# PAC1720_Breakout.net
KiCad netlist of a schematic drawn in EAGLE
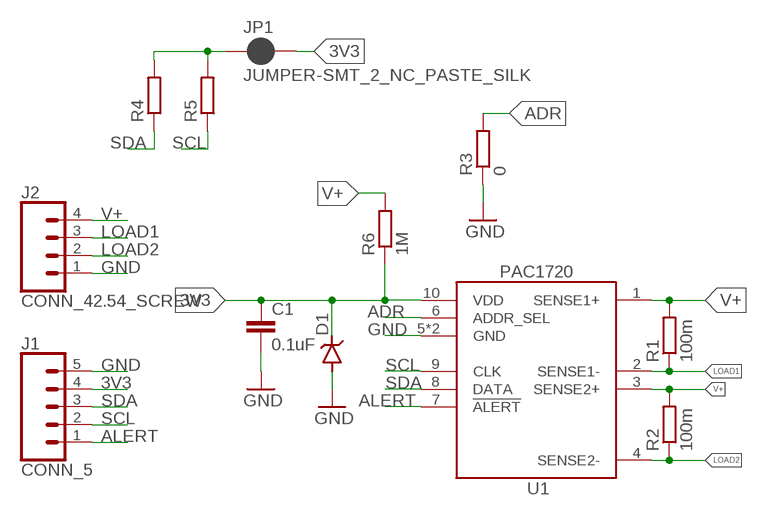
[diagram p0: schematic, sheet 1]

(export (version "E")
  (design (tool "Eeschema 10.0.6"))
  (components
    (comp (ref "C1")
      (value "0.1uF")
      (footprint "eagle-import:C0402")
      (fields (field (name "MF") "Murata") (field (name "MPN") "GCM155R71C104KA55D"))
      (libsource (lib "eagle-import") (part "C-EUC04020.1UF"))
    )
    (comp (ref "D1")
      (value "DIODE_ZENERSOD-123")
      (footprint "eagle-import:SOD-123")
      (fields
        (field (name "DIGIKEY") "MMSZ5231B-FDICT-ND")
        (field (name "MF") "Diodes Incorporated")
        (field (name "MPN") "MMSZ5231B-7-F")
      )
      (libsource (lib "eagle-import") (part "DIODE_ZENERSOD-123"))
    )
    (comp (ref "J1")
      (value "CONN_5")
      (footprint "eagle-import:1X05")
      (fields (field (name "MF") "On Shore") (field (name "MPN") "OSTVN05A150"))
      (libsource (lib "eagle-import") (part "CONN_5"))
    )
    (comp (ref "J2")
      (value "CONN_42.54_SCREW")
      (footprint "eagle-import:1X04_SCREW")
      (fields (field (name "MF") "On Shore") (field (name "MPN") "OSTVN04A150"))
      (libsource (lib "eagle-import") (part "CONN_42.54_SCREW"))
    )
    (comp (ref "JP1")
      (value "JUMPER-SMT_2_NC_PASTE_SILK")
      (footprint "eagle-import:SMT-JUMPER_2_NC_PASTE_SILK")
      (libsource (lib "eagle-import") (part "JUMPER-SMT_2_NC_PASTE_SILK"))
    )
    (comp (ref "R1")
      (value "100m")
      (footprint "eagle-import:R0805")
      (fields (field (name "MF") "Panasonic") (field (name "MPN") "ERJ-6DSFR10V"))
      (libsource (lib "eagle-import") (part "R-EU_R08050.1"))
    )
    (comp (ref "R2")
      (value "100m")
      (footprint "eagle-import:R0805")
      (fields (field (name "MF") "Panasonic") (field (name "MPN") "ERJ-6DSFR10V"))
      (libsource (lib "eagle-import") (part "R-EU_R08050.1"))
    )
    (comp (ref "R3")
      (value "0")
      (footprint "eagle-import:R0402")
      (fields (field (name "MF") "Yageo") (field (name "MPN") "RC0402JR-070RL"))
      (libsource (lib "eagle-import") (part "R-EU_R04020.0"))
    )
    (comp (ref "R4")
      (value "R-EU_10KR0402")
      (footprint "eagle-import:R0402")
      (fields
        (field (name "MF") "Yageo")
        (field (name "MPN") "RC0402FR-0710KL")
        (field (name "VALUE_PART") "10k")
      )
      (libsource (lib "eagle-import") (part "R-EU_R040210K"))
    )
    (comp (ref "R5")
      (value "R-EU_10KR0402")
      (footprint "eagle-import:R0402")
      (fields
        (field (name "MF") "Yageo")
        (field (name "MPN") "RC0402FR-0710KL")
        (field (name "VALUE_PART") "10k")
      )
      (libsource (lib "eagle-import") (part "R-EU_R040210K"))
    )
    (comp (ref "R6")
      (value "1M")
      (footprint "eagle-import:R0402")
      (fields (field (name "MF") "Yageo") (field (name "MPN") "RC0402FR-071ML"))
      (libsource (lib "eagle-import") (part "R-EU_R04021M"))
    )
    (comp (ref "U1")
      (value "PAC1720")
      (footprint "eagle-import:VDFN-10")
      (fields (field (name "MF") "Microchip") (field (name "MPN") "PAC1720-1-AIA-TR"))
      (libsource (lib "eagle-import") (part "PAC1720"))
    )
  )
  (nets
    (net (code "1") (name "/ALERT") (class "Default")
      (node (ref "J1") (pin "1") (pinfunction "1_1") (pintype "passive"))
      (node (ref "U1") (pin "7") (pinfunction "~{ALERT}_7") (pintype "output"))
    )
    (net (code "2") (name "/SCL") (class "Default")
      (node (ref "J1") (pin "2") (pinfunction "2_2") (pintype "passive"))
      (node (ref "R5") (pin "1") (pinfunction "1_1") (pintype "passive"))
      (node (ref "U1") (pin "9") (pinfunction "CLK_9") (pintype "input"))
    )
    (net (code "3") (name "/SDA") (class "Default")
      (node (ref "J1") (pin "3") (pinfunction "3_3") (pintype "passive"))
      (node (ref "R4") (pin "1") (pinfunction "1_1") (pintype "passive"))
      (node (ref "U1") (pin "8") (pinfunction "DATA_8") (pintype "bidirectional"))
    )
    (net (code "4") (name "3V3") (class "Default")
      (node (ref "C1") (pin "1") (pinfunction "1_1") (pintype "passive"))
      (node (ref "D1") (pin "CAT") (pinfunction "C_CAT") (pintype "passive"))
      (node (ref "J1") (pin "4") (pinfunction "4_4") (pintype "passive"))
      (node (ref "JP1") (pin "2") (pinfunction "2_2") (pintype "passive"))
      (node (ref "R6") (pin "1") (pinfunction "1_1") (pintype "passive"))
      (node (ref "U1") (pin "10") (pinfunction "VDD_10") (pintype "power_in"))
    )
    (net (code "5") (name "ADR") (class "Default")
      (node (ref "R3") (pin "2") (pinfunction "2_2") (pintype "passive"))
      (node (ref "U1") (pin "6") (pinfunction "ADDR_SEL_6") (pintype "input"))
    )
    (net (code "6") (name "GND") (class "Default")
      (node (ref "C1") (pin "2") (pinfunction "2_2") (pintype "passive"))
      (node (ref "D1") (pin "ANODE") (pinfunction "A_ANODE") (pintype "passive"))
      (node (ref "J1") (pin "5") (pinfunction "5_5") (pintype "passive"))
      (node (ref "J2") (pin "1") (pinfunction "1_1") (pintype "passive"))
      (node (ref "R3") (pin "1") (pinfunction "1_1") (pintype "passive"))
      (node (ref "U1") (pin "5") (pinfunction "GND_5") (pintype "power_in"))
      (node (ref "U1") (pin "EP") (pinfunction "GND_EP") (pintype "power_in"))
    )
    (net (code "7") (name "LOAD1") (class "Default")
      (node (ref "J2") (pin "3") (pinfunction "3_3") (pintype "passive"))
      (node (ref "R1") (pin "1") (pinfunction "1_1") (pintype "passive"))
      (node (ref "U1") (pin "2") (pinfunction "SENSE1-_2") (pintype "input"))
    )
    (net (code "8") (name "LOAD2") (class "Default")
      (node (ref "J2") (pin "2") (pinfunction "2_2") (pintype "passive"))
      (node (ref "R2") (pin "1") (pinfunction "1_1") (pintype "passive"))
      (node (ref "U1") (pin "4") (pinfunction "SENSE2-_4") (pintype "input"))
    )
    (net (code "9") (name "Net-(JP1-Pad1)") (class "Default")
      (node (ref "JP1") (pin "1") (pinfunction "1_1") (pintype "passive"))
      (node (ref "R4") (pin "2") (pinfunction "2_2") (pintype "passive"))
      (node (ref "R5") (pin "2") (pinfunction "2_2") (pintype "passive"))
    )
    (net (code "10") (name "V+") (class "Default")
      (node (ref "J2") (pin "4") (pinfunction "4_4") (pintype "passive"))
      (node (ref "R1") (pin "2") (pinfunction "2_2") (pintype "passive"))
      (node (ref "R2") (pin "2") (pinfunction "2_2") (pintype "passive"))
      (node (ref "R6") (pin "2") (pinfunction "2_2") (pintype "passive"))
      (node (ref "U1") (pin "1") (pinfunction "SENSE1+_1") (pintype "input"))
      (node (ref "U1") (pin "3") (pinfunction "SENSE2+_3") (pintype "input"))
    )
  )
)
